# plugV15-smd-5x5cm-C-swap-zener.net
KiCad netlist of a schematic drawn in EAGLE
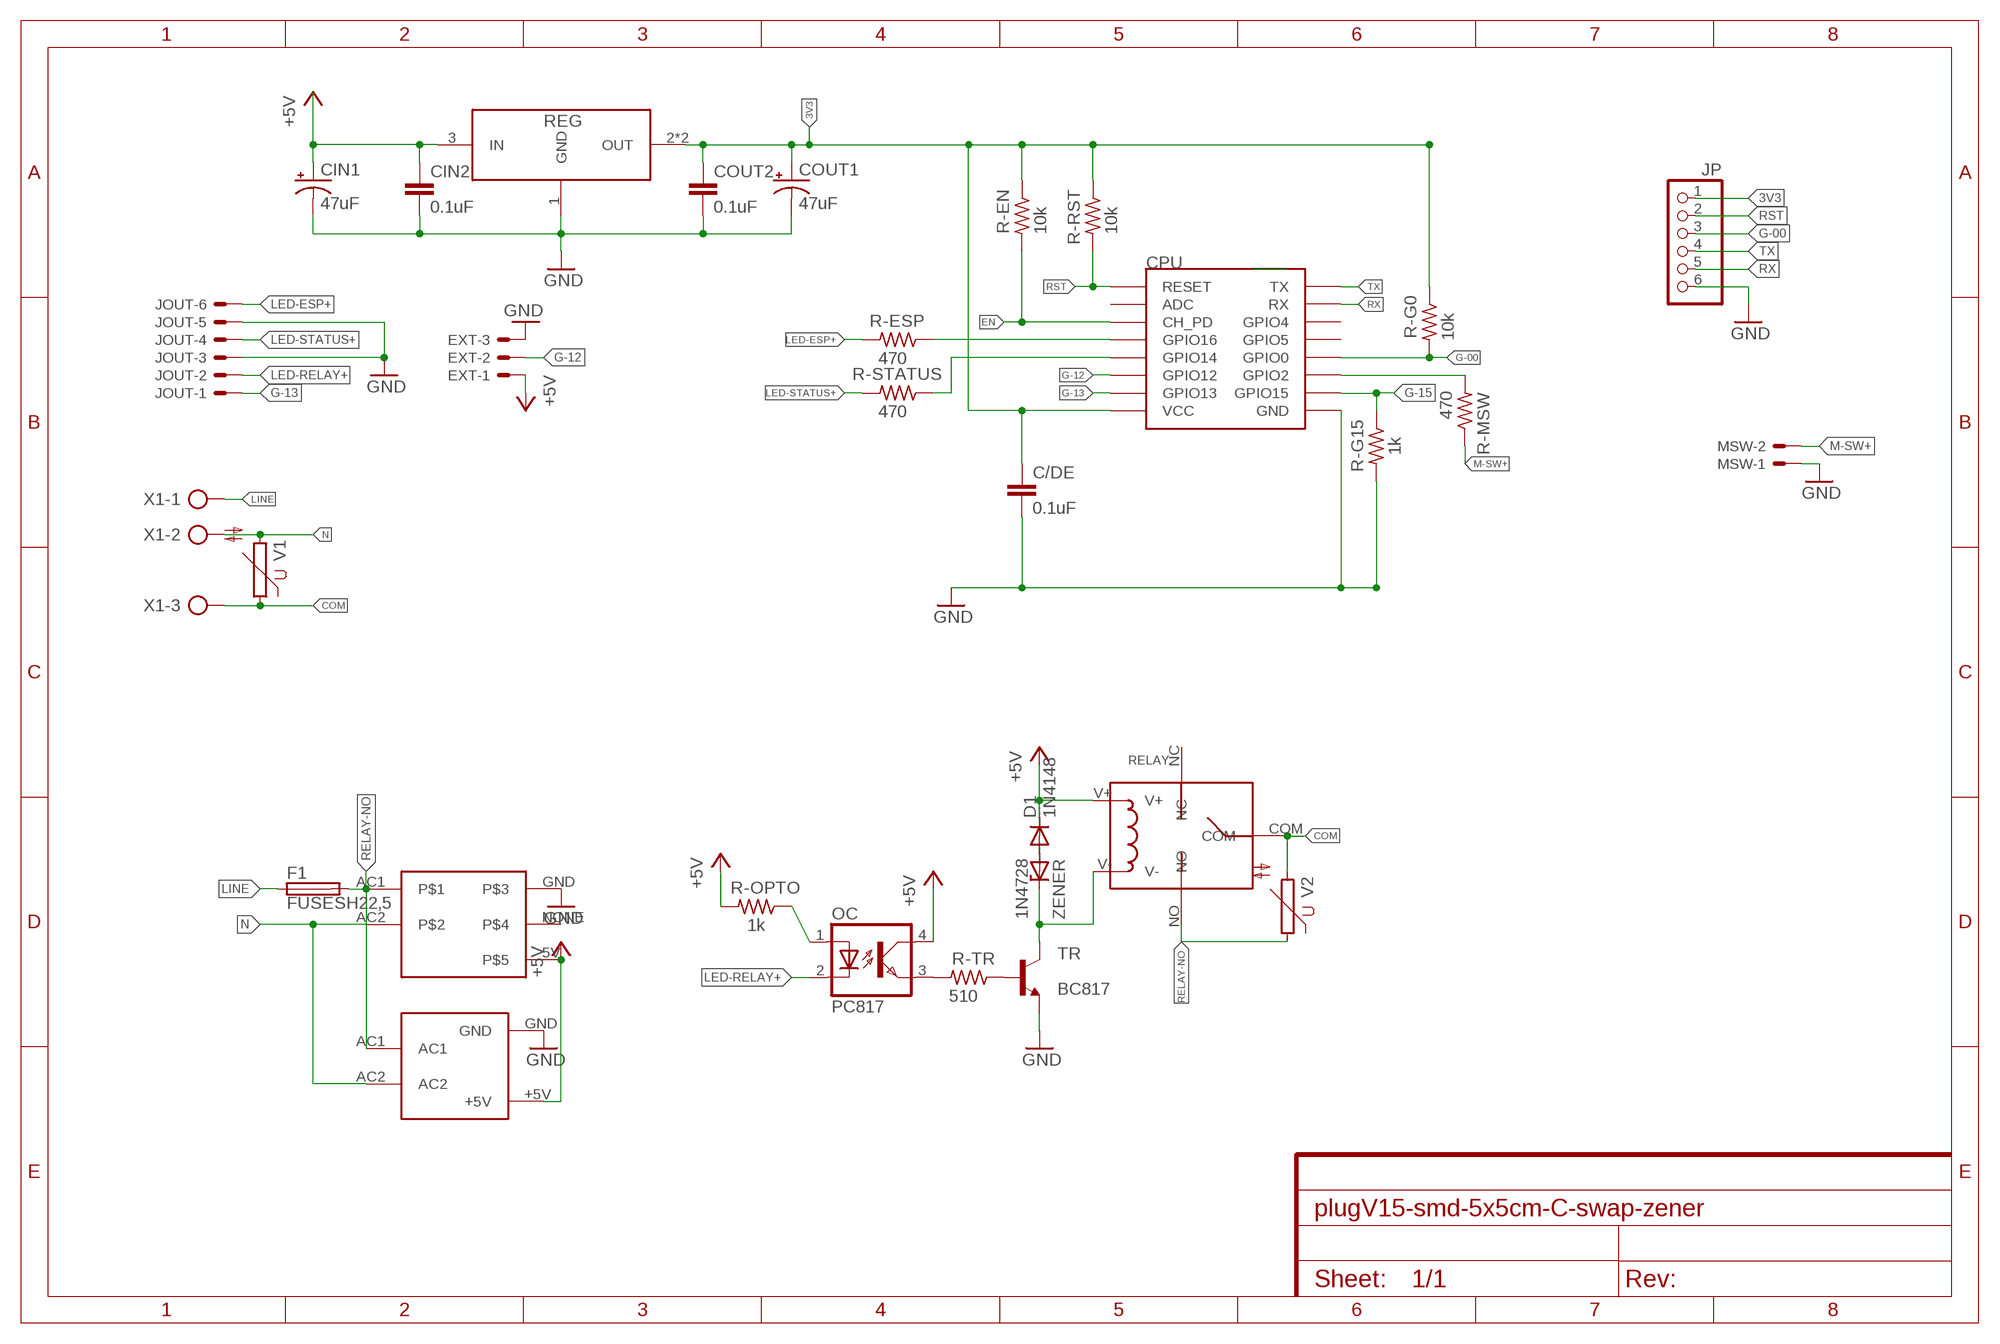
[diagram p0: schematic, sheet 1]

(export (version "E")
  (design (tool "Eeschema 10.0.6"))
  (components
    (comp (ref "C/DE")
      (value "0.1uF")
      (footprint "eagle-import:C0805")
      (libsource (lib "eagle-import") (part "C-EUC0805"))
    )
    (comp (ref "CIN1")
      (value "47uF")
      (footprint "eagle-import:E2,5-5")
      (libsource (lib "eagle-import") (part "CPOL-USE2.5-5"))
    )
    (comp (ref "CIN2")
      (value "0.1uF")
      (footprint "eagle-import:C0805")
      (libsource (lib "eagle-import") (part "C-EUC0805"))
    )
    (comp (ref "COUT1")
      (value "47uF")
      (footprint "eagle-import:E2,5-5")
      (libsource (lib "eagle-import") (part "CPOL-USE2.5-5"))
    )
    (comp (ref "COUT2")
      (value "0.1uF")
      (footprint "eagle-import:C0805")
      (libsource (lib "eagle-import") (part "C-EUC0805"))
    )
    (comp (ref "CPU")
      (value "ESP12SMD")
      (footprint "eagle-import:ESP12-SMD")
      (libsource (lib "eagle-import") (part "ESP12SMD"))
    )
    (comp (ref "D1")
      (value "1N4148")
      (footprint "eagle-import:DO35-7")
      (libsource (lib "eagle-import") (part "1N4148DO35-7"))
    )
    (comp (ref "EXT")
      (value "53048-03")
      (footprint "eagle-import:53048-03")
      (fields (field (name "MF") "WALDOM/MOLEX") (field (name "MPN") "53048-0310"))
      (libsource (lib "eagle-import") (part "53?-03048"))
    )
    (comp (ref "F1")
      (value "FUSESH22,5")
      (footprint "eagle-import:SH22,5")
      (libsource (lib "eagle-import") (part "FUSESH22,5"))
    )
    (comp (ref "HLK")
      (value "HLK-PM01")
      (footprint "eagle-import:HLK-PM01")
      (libsource (lib "eagle-import") (part "HLK-PM01"))
    )
    (comp (ref "JOUT")
      (value "53048-06")
      (footprint "eagle-import:53048-06")
      (fields (field (name "MF") "WALDOM/MOLEX") (field (name "MPN") "53048-0610"))
      (libsource (lib "eagle-import") (part "53?-06048"))
    )
    (comp (ref "JP")
      (value "PINHD-1X6")
      (footprint "eagle-import:1X06")
      (libsource (lib "eagle-import") (part "PINHD-1X6"))
    )
    (comp (ref "MSW")
      (value "53048-02")
      (footprint "eagle-import:53048-02")
      (fields (field (name "MF") "MOLEX") (field (name "MPN") "53048-0210"))
      (libsource (lib "eagle-import") (part "53?-02048"))
    )
    (comp (ref "OC")
      (value "PC817")
      (footprint "eagle-import:DIL04")
      (fields (field (name "MPN") "PC817X4J000F"))
      (libsource (lib "eagle-import") (part "PC817"))
    )
    (comp (ref "R-EN")
      (value "10k")
      (footprint "eagle-import:M0805")
      (libsource (lib "eagle-import") (part "R-US_M0805"))
    )
    (comp (ref "R-ESP")
      (value "470")
      (footprint "eagle-import:M0805")
      (libsource (lib "eagle-import") (part "R-US_M0805"))
    )
    (comp (ref "R-G0")
      (value "10k")
      (footprint "eagle-import:M0805")
      (libsource (lib "eagle-import") (part "R-US_M0805"))
    )
    (comp (ref "R-G15")
      (value "1k")
      (footprint "eagle-import:M0805")
      (libsource (lib "eagle-import") (part "R-US_M0805"))
    )
    (comp (ref "R-MSW")
      (value "470")
      (footprint "eagle-import:M0805")
      (libsource (lib "eagle-import") (part "R-US_M0805"))
    )
    (comp (ref "R-OPTO")
      (value "1k")
      (footprint "eagle-import:M0805")
      (libsource (lib "eagle-import") (part "R-US_M0805"))
    )
    (comp (ref "R-RST")
      (value "10k")
      (footprint "eagle-import:M0805")
      (libsource (lib "eagle-import") (part "R-US_M0805"))
    )
    (comp (ref "R-STATUS")
      (value "470")
      (footprint "eagle-import:M0805")
      (libsource (lib "eagle-import") (part "R-US_M0805"))
    )
    (comp (ref "R-TR")
      (value "510")
      (footprint "eagle-import:M0805")
      (libsource (lib "eagle-import") (part "R-US_M0805"))
    )
    (comp (ref "REG")
      (value "AMS1117-3.3")
      (footprint "eagle-import:SOT-223")
      (libsource (lib "eagle-import") (part "AMS1117-3.3"))
    )
    (comp (ref "RELAY")
      (value "RELAY-SONGLE")
      (footprint "eagle-import:RELAY-SONGLE")
      (libsource (lib "eagle-import") (part "RELAY-SONGLE"))
    )
    (comp (ref "TR")
      (value "BC817")
      (footprint "eagle-import:SOT23-BEC")
      (libsource (lib "eagle-import") (part "BC817SMD-16"))
    )
    (comp (ref "U$4")
      (value "POWERSUPPLY-5V-700MA")
      (footprint "eagle-import:POWERSUPPLY-5V-700MA")
      (libsource (lib "eagle-import") (part "POWERSUPPLY-5V-700MA"))
    )
    (comp (ref "V1")
      (value "S14K11")
      (footprint "eagle-import:S14K11")
      (libsource (lib "eagle-import") (part "S14K11"))
    )
    (comp (ref "V2")
      (value "S14K11")
      (footprint "eagle-import:S14K11")
      (libsource (lib "eagle-import") (part "S14K11"))
    )
    (comp (ref "X1")
      (value "AK300/3")
      (footprint "eagle-import:AK300_3")
      (libsource (lib "eagle-import") (part "AK300/3"))
    )
    (comp (ref "ZENER")
      (value "1N4728")
      (footprint "eagle-import:DO41Z10")
      (libsource (lib "eagle-import") (part "1N4728"))
    )
  )
  (nets
    (net (code "1") (name "+5V") (class "Default")
      (node (ref "CIN1") (pin "+") (pinfunction "+_+") (pintype "passive"))
      (node (ref "CIN2") (pin "1") (pinfunction "1_1") (pintype "passive"))
      (node (ref "D1") (pin "C") (pinfunction "C_C") (pintype "passive"))
      (node (ref "EXT") (pin "1") (pinfunction "S_1") (pintype "passive"))
      (node (ref "HLK") (pin "+5V") (pinfunction "+5V_+5V") (pintype "bidirectional"))
      (node (ref "OC") (pin "4") (pinfunction "COL_4") (pintype "passive"))
      (node (ref "R-OPTO") (pin "2") (pinfunction "2_2") (pintype "passive"))
      (node (ref "REG") (pin "3") (pinfunction "IN_3") (pintype "input"))
      (node (ref "RELAY") (pin "V+") (pinfunction "V+_V+") (pintype "bidirectional"))
      (node (ref "U$4") (pin "5V") (pinfunction "P$5_5V") (pintype "bidirectional"))
    )
    (net (code "2") (name "3V3") (class "Default")
      (node (ref "C/DE") (pin "1") (pinfunction "1_1") (pintype "passive"))
      (node (ref "COUT1") (pin "+") (pinfunction "+_+") (pintype "passive"))
      (node (ref "COUT2") (pin "1") (pinfunction "1_1") (pintype "passive"))
      (node (ref "CPU") (pin "VCC") (pinfunction "VCC_VCC") (pintype "bidirectional"))
      (node (ref "JP") (pin "1") (pinfunction "1_1") (pintype "passive"))
      (node (ref "R-EN") (pin "1") (pinfunction "1_1") (pintype "passive"))
      (node (ref "R-G0") (pin "1") (pinfunction "1_1") (pintype "passive"))
      (node (ref "R-RST") (pin "1") (pinfunction "1_1") (pintype "passive"))
      (node (ref "REG") (pin "2") (pinfunction "OUT_2") (pintype "output"))
      (node (ref "REG") (pin "4") (pinfunction "OUT_4") (pintype "output"))
    )
    (net (code "3") (name "COM") (class "Default")
      (node (ref "RELAY") (pin "COM") (pinfunction "COM_COM") (pintype "bidirectional"))
      (node (ref "V1") (pin "1") (pinfunction "1_1") (pintype "passive"))
      (node (ref "V2") (pin "2") (pinfunction "2_2") (pintype "passive"))
      (node (ref "X1") (pin "3") (pinfunction "KL_3") (pintype "passive"))
    )
    (net (code "4") (name "EN") (class "Default")
      (node (ref "CPU") (pin "CH_PD") (pinfunction "CH_PD_CH_PD") (pintype "bidirectional"))
      (node (ref "R-EN") (pin "2") (pinfunction "2_2") (pintype "passive"))
    )
    (net (code "5") (name "G-00") (class "Default")
      (node (ref "CPU") (pin "GPIO0") (pinfunction "GPIO0_GPIO0") (pintype "bidirectional"))
      (node (ref "JP") (pin "3") (pinfunction "3_3") (pintype "passive"))
      (node (ref "R-G0") (pin "2") (pinfunction "2_2") (pintype "passive"))
    )
    (net (code "6") (name "G-12") (class "Default")
      (node (ref "CPU") (pin "GPIO12") (pinfunction "GPIO12_GPIO12") (pintype "bidirectional"))
      (node (ref "EXT") (pin "2") (pinfunction "S_2") (pintype "passive"))
    )
    (net (code "7") (name "G-13") (class "Default")
      (node (ref "CPU") (pin "GPIO13") (pinfunction "GPIO13_GPIO13") (pintype "bidirectional"))
      (node (ref "JOUT") (pin "1") (pinfunction "S_1") (pintype "passive"))
    )
    (net (code "8") (name "G-15") (class "Default")
      (node (ref "CPU") (pin "GPIO15") (pinfunction "GPIO15_GPIO15") (pintype "bidirectional"))
      (node (ref "R-G15") (pin "1") (pinfunction "1_1") (pintype "passive"))
    )
    (net (code "9") (name "GND") (class "Default")
      (node (ref "C/DE") (pin "2") (pinfunction "2_2") (pintype "passive"))
      (node (ref "CIN1") (pin "-") (pinfunction "-_-") (pintype "passive"))
      (node (ref "CIN2") (pin "2") (pinfunction "2_2") (pintype "passive"))
      (node (ref "COUT1") (pin "-") (pinfunction "-_-") (pintype "passive"))
      (node (ref "COUT2") (pin "2") (pinfunction "2_2") (pintype "passive"))
      (node (ref "CPU") (pin "GND") (pinfunction "GND_GND") (pintype "bidirectional"))
      (node (ref "EXT") (pin "3") (pinfunction "S_3") (pintype "passive"))
      (node (ref "HLK") (pin "GND") (pinfunction "GND_GND") (pintype "bidirectional"))
      (node (ref "JOUT") (pin "3") (pinfunction "S_3") (pintype "passive"))
      (node (ref "JOUT") (pin "5") (pinfunction "S_5") (pintype "passive"))
      (node (ref "JP") (pin "6") (pinfunction "6_6") (pintype "passive"))
      (node (ref "MSW") (pin "1") (pinfunction "S_1") (pintype "passive"))
      (node (ref "R-G15") (pin "2") (pinfunction "2_2") (pintype "passive"))
      (node (ref "REG") (pin "1") (pinfunction "GND_1") (pintype "passive"))
      (node (ref "TR") (pin "E") (pinfunction "E_E") (pintype "passive"))
      (node (ref "U$4") (pin "GND") (pinfunction "P$3_GND") (pintype "bidirectional"))
    )
    (net (code "10") (name "LED-ESP+") (class "Default")
      (node (ref "JOUT") (pin "6") (pinfunction "S_6") (pintype "passive"))
      (node (ref "R-ESP") (pin "2") (pinfunction "2_2") (pintype "passive"))
    )
    (net (code "11") (name "LED-RELAY+") (class "Default")
      (node (ref "JOUT") (pin "2") (pinfunction "S_2") (pintype "passive"))
      (node (ref "OC") (pin "2") (pinfunction "C_2") (pintype "passive"))
    )
    (net (code "12") (name "LED-STATUS+") (class "Default")
      (node (ref "JOUT") (pin "4") (pinfunction "S_4") (pintype "passive"))
      (node (ref "R-STATUS") (pin "2") (pinfunction "2_2") (pintype "passive"))
    )
    (net (code "13") (name "LINE") (class "Default")
      (node (ref "F1") (pin "1") (pinfunction "1_1") (pintype "passive"))
      (node (ref "X1") (pin "1") (pinfunction "KL_1") (pintype "passive"))
    )
    (net (code "14") (name "M-SW+") (class "Default")
      (node (ref "MSW") (pin "2") (pinfunction "S_2") (pintype "passive"))
      (node (ref "R-MSW") (pin "1") (pinfunction "1_1") (pintype "passive"))
    )
    (net (code "15") (name "N") (class "Default")
      (node (ref "HLK") (pin "AC2") (pinfunction "AC2_AC2") (pintype "bidirectional"))
      (node (ref "U$4") (pin "AC2") (pinfunction "P$2_AC2") (pintype "bidirectional"))
      (node (ref "V1") (pin "2") (pinfunction "2_2") (pintype "passive"))
      (node (ref "X1") (pin "2") (pinfunction "KL_2") (pintype "passive"))
    )
    (net (code "16") (name "Net-(CPU-PadGPIO2)") (class "Default")
      (node (ref "CPU") (pin "GPIO2") (pinfunction "GPIO2_GPIO2") (pintype "bidirectional"))
      (node (ref "R-MSW") (pin "2") (pinfunction "2_2") (pintype "passive"))
    )
    (net (code "17") (name "Net-(CPU-PadGPIO14)") (class "Default")
      (node (ref "CPU") (pin "GPIO14") (pinfunction "GPIO14_GPIO14") (pintype "bidirectional"))
      (node (ref "R-STATUS") (pin "1") (pinfunction "1_1") (pintype "passive"))
    )
    (net (code "18") (name "Net-(CPU-PadGPIO16)") (class "Default")
      (node (ref "CPU") (pin "GPIO16") (pinfunction "GPIO16_GPIO16") (pintype "bidirectional"))
      (node (ref "R-ESP") (pin "1") (pinfunction "1_1") (pintype "passive"))
    )
    (net (code "19") (name "Net-(D1-PadA)") (class "Default")
      (node (ref "D1") (pin "A") (pinfunction "A_A") (pintype "passive"))
      (node (ref "ZENER") (pin "A") (pinfunction "A_A") (pintype "passive"))
    )
    (net (code "20") (name "Net-(OC-A)") (class "Default")
      (node (ref "OC") (pin "1") (pinfunction "A_1") (pintype "passive"))
      (node (ref "R-OPTO") (pin "1") (pinfunction "1_1") (pintype "passive"))
    )
    (net (code "21") (name "Net-(OC-EMIT)") (class "Default")
      (node (ref "OC") (pin "3") (pinfunction "EMIT_3") (pintype "passive"))
      (node (ref "R-TR") (pin "2") (pinfunction "2_2") (pintype "passive"))
    )
    (net (code "22") (name "Net-(R-TR-Pad1)") (class "Default")
      (node (ref "R-TR") (pin "1") (pinfunction "1_1") (pintype "passive"))
      (node (ref "TR") (pin "B") (pinfunction "B_B") (pintype "passive"))
    )
    (net (code "23") (name "Net-(RELAY-PadV-)") (class "Default")
      (node (ref "RELAY") (pin "V-") (pinfunction "V-_V-") (pintype "bidirectional"))
      (node (ref "TR") (pin "C") (pinfunction "C_C") (pintype "passive"))
      (node (ref "ZENER") (pin "C") (pinfunction "C_C") (pintype "passive"))
    )
    (net (code "24") (name "RELAY-NO") (class "Default")
      (node (ref "F1") (pin "2") (pinfunction "2_2") (pintype "passive"))
      (node (ref "HLK") (pin "AC1") (pinfunction "AC1_AC1") (pintype "bidirectional"))
      (node (ref "RELAY") (pin "NO") (pinfunction "NO_NO") (pintype "bidirectional"))
      (node (ref "U$4") (pin "AC1") (pinfunction "P$1_AC1") (pintype "bidirectional"))
      (node (ref "V2") (pin "1") (pinfunction "1_1") (pintype "passive"))
    )
    (net (code "25") (name "RST") (class "Default")
      (node (ref "CPU") (pin "RESET") (pinfunction "RESET_RESET") (pintype "bidirectional"))
      (node (ref "JP") (pin "2") (pinfunction "2_2") (pintype "passive"))
      (node (ref "R-RST") (pin "2") (pinfunction "2_2") (pintype "passive"))
    )
    (net (code "26") (name "RX") (class "Default")
      (node (ref "CPU") (pin "RXD0") (pinfunction "RX_RXD0") (pintype "bidirectional"))
      (node (ref "JP") (pin "5") (pinfunction "5_5") (pintype "passive"))
    )
    (net (code "27") (name "TX") (class "Default")
      (node (ref "CPU") (pin "TXD0") (pinfunction "TX_TXD0") (pintype "bidirectional"))
      (node (ref "JP") (pin "4") (pinfunction "4_4") (pintype "passive"))
    )
    (net (code "28") (name "unconnected-(CPU-PadADC)") (class "Default")
      (node (ref "CPU") (pin "ADC") (pinfunction "ADC_ADC") (pintype "bidirectional"))
    )
    (net (code "29") (name "unconnected-(CPU-PadGPIO4)") (class "Default")
      (node (ref "CPU") (pin "GPIO4") (pinfunction "GPIO4_GPIO4") (pintype "bidirectional"))
    )
    (net (code "30") (name "unconnected-(CPU-PadGPIO5)") (class "Default")
      (node (ref "CPU") (pin "GPIO5") (pinfunction "GPIO5_GPIO5") (pintype "bidirectional"))
    )
    (net (code "31") (name "unconnected-(RELAY-PadNC)") (class "Default")
      (node (ref "RELAY") (pin "NC") (pinfunction "NC_NC") (pintype "bidirectional"))
    )
    (net (code "32") (name "unconnected-(U$4-P$4-PadNONE)") (class "Default")
      (node (ref "U$4") (pin "NONE") (pinfunction "P$4_NONE") (pintype "bidirectional"))
    )
  )
)
